# Iridium_9603N_Solar_Beacon.net
KiCad netlist of a schematic drawn in EAGLE
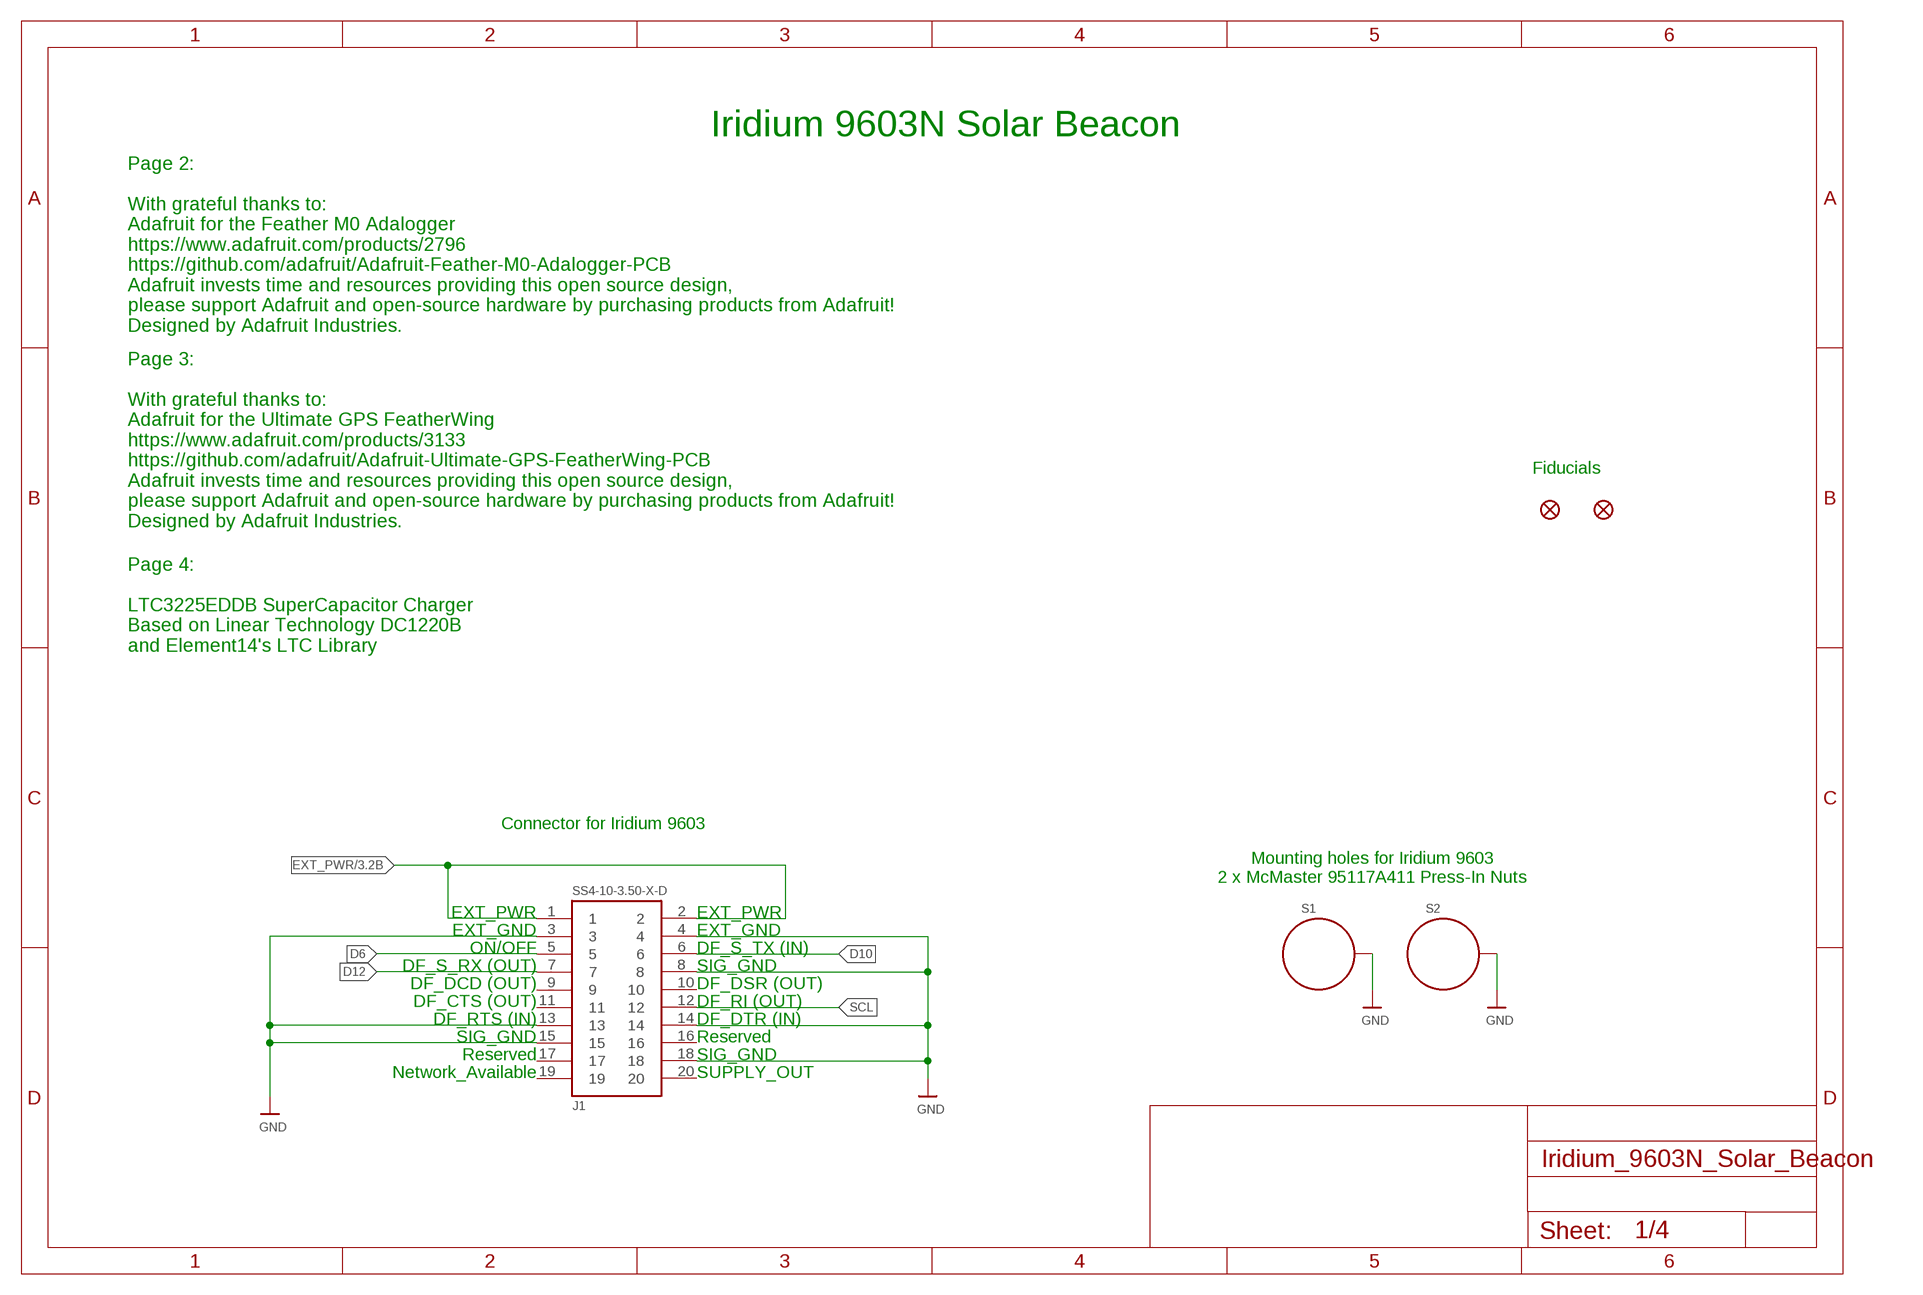
[diagram p0: schematic, sheet 1]
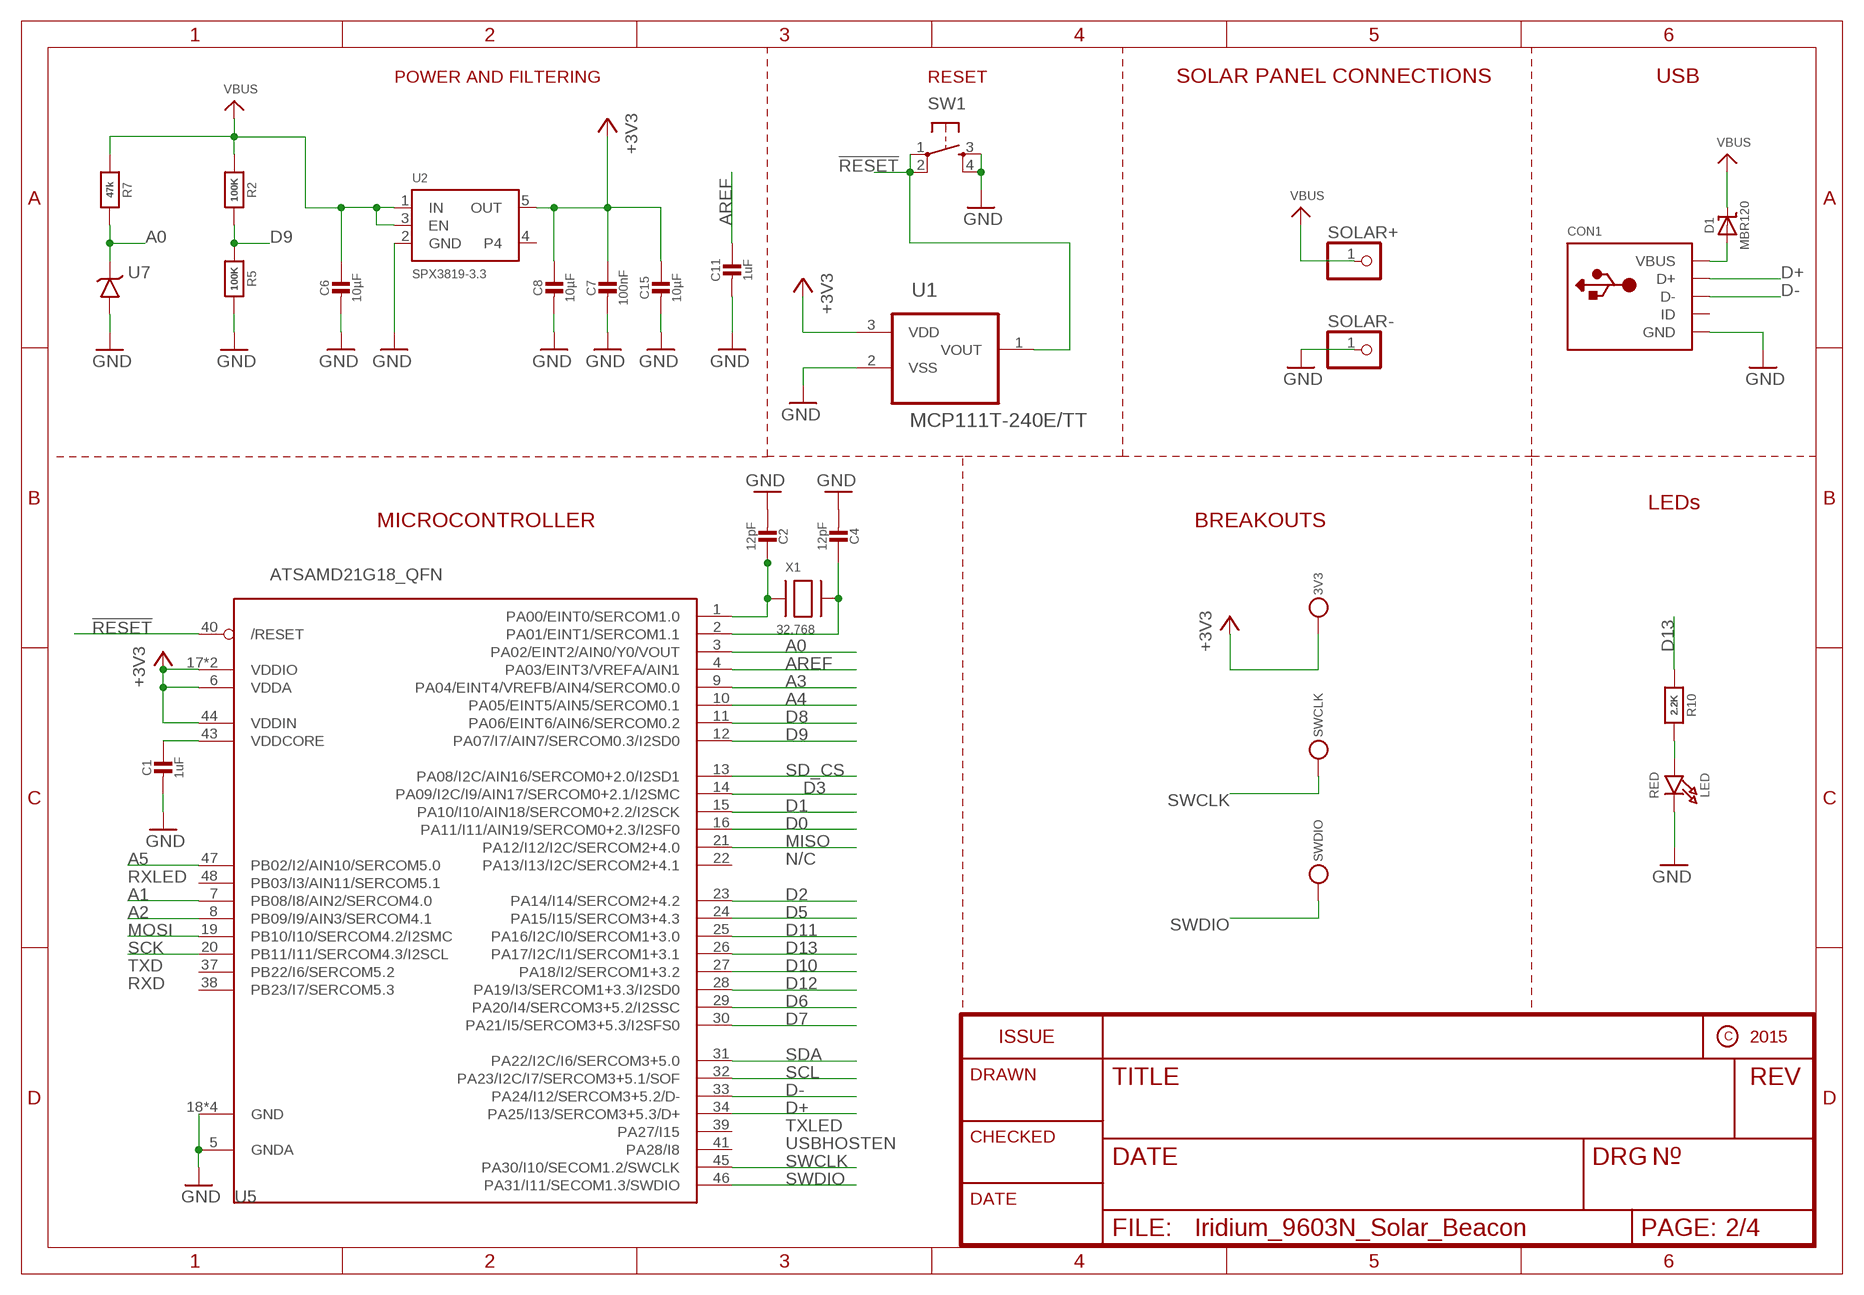
[diagram p1: schematic, sheet 2]
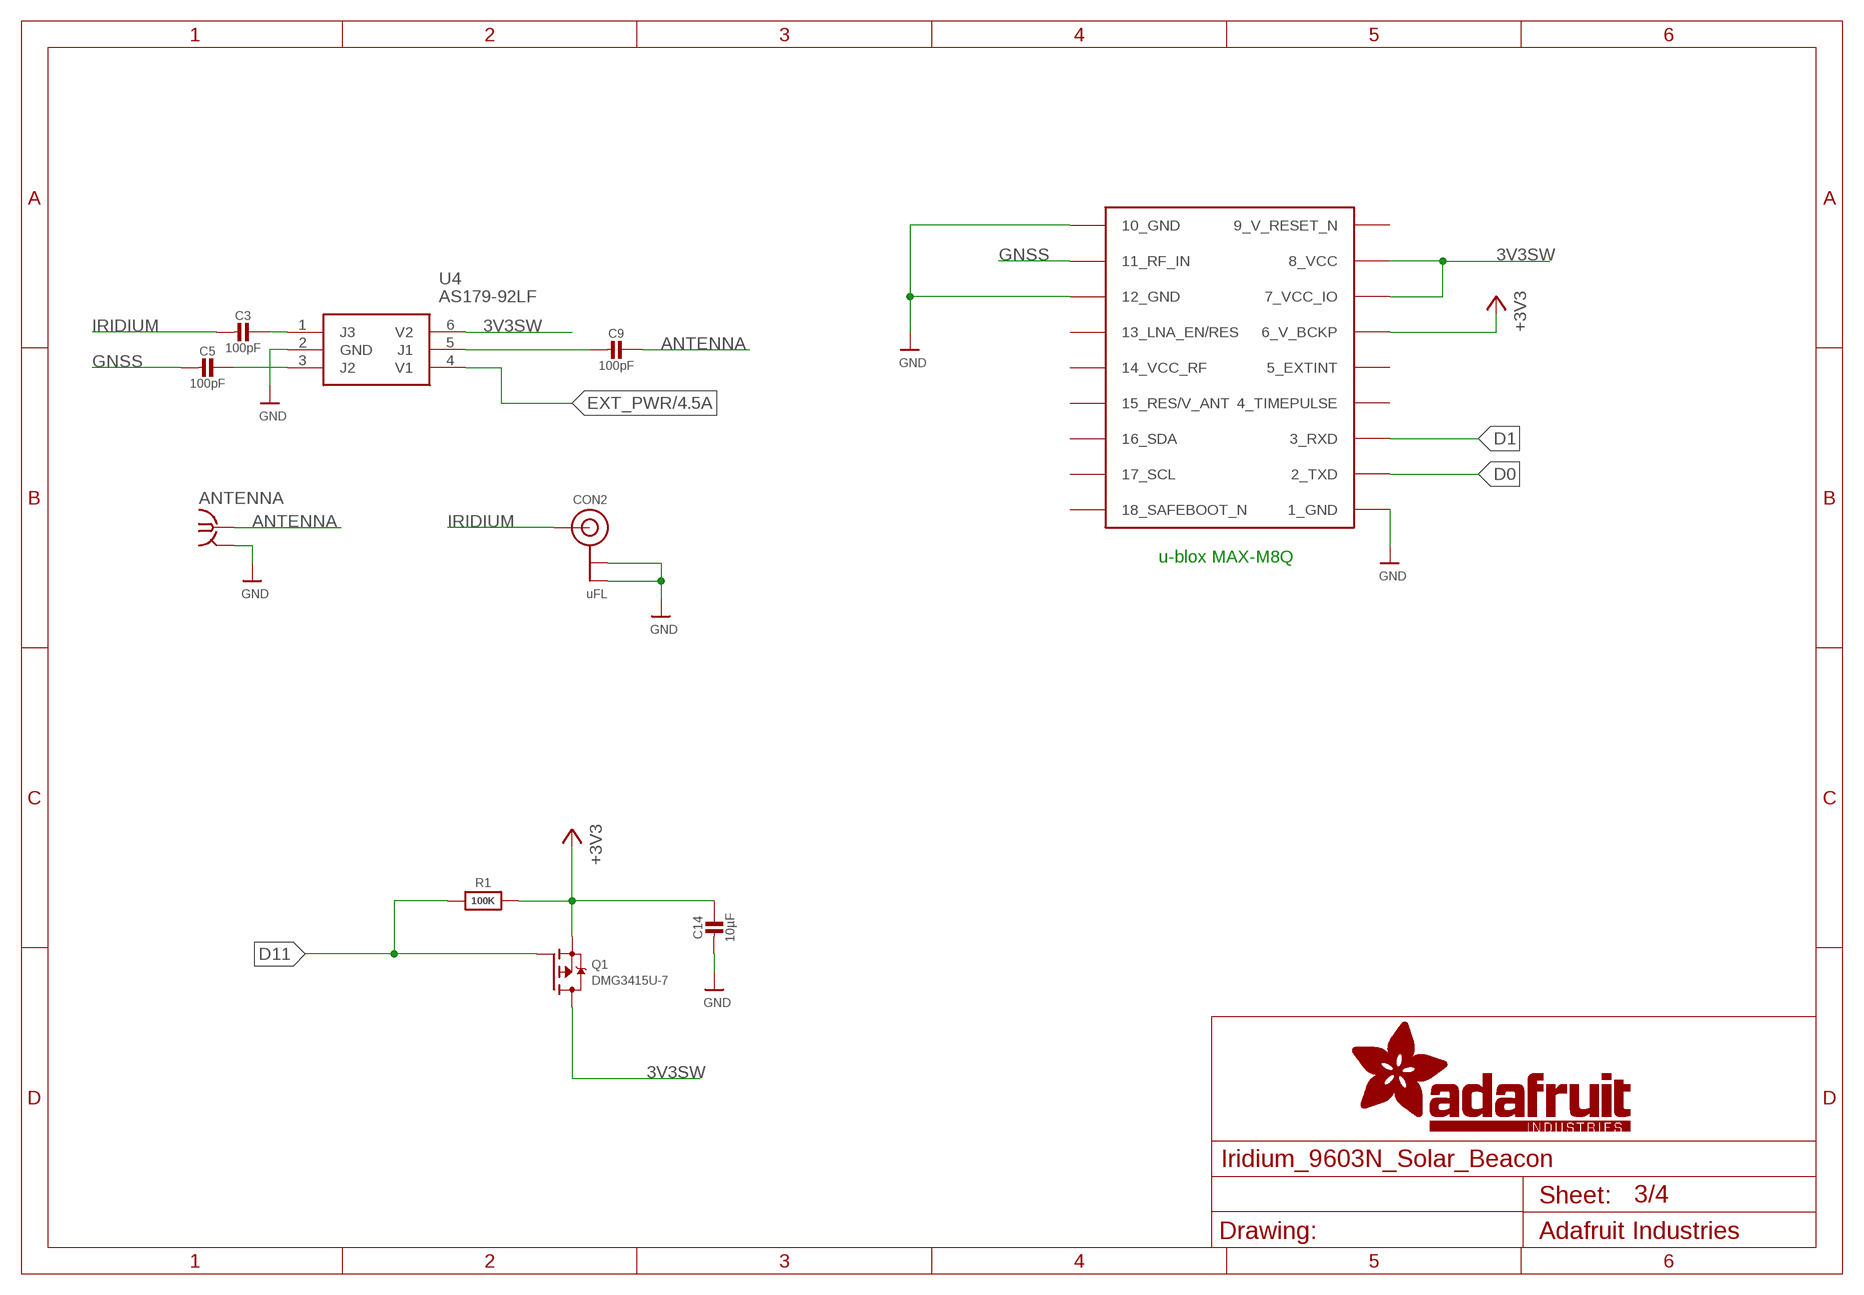
[diagram p2: schematic, sheet 3]
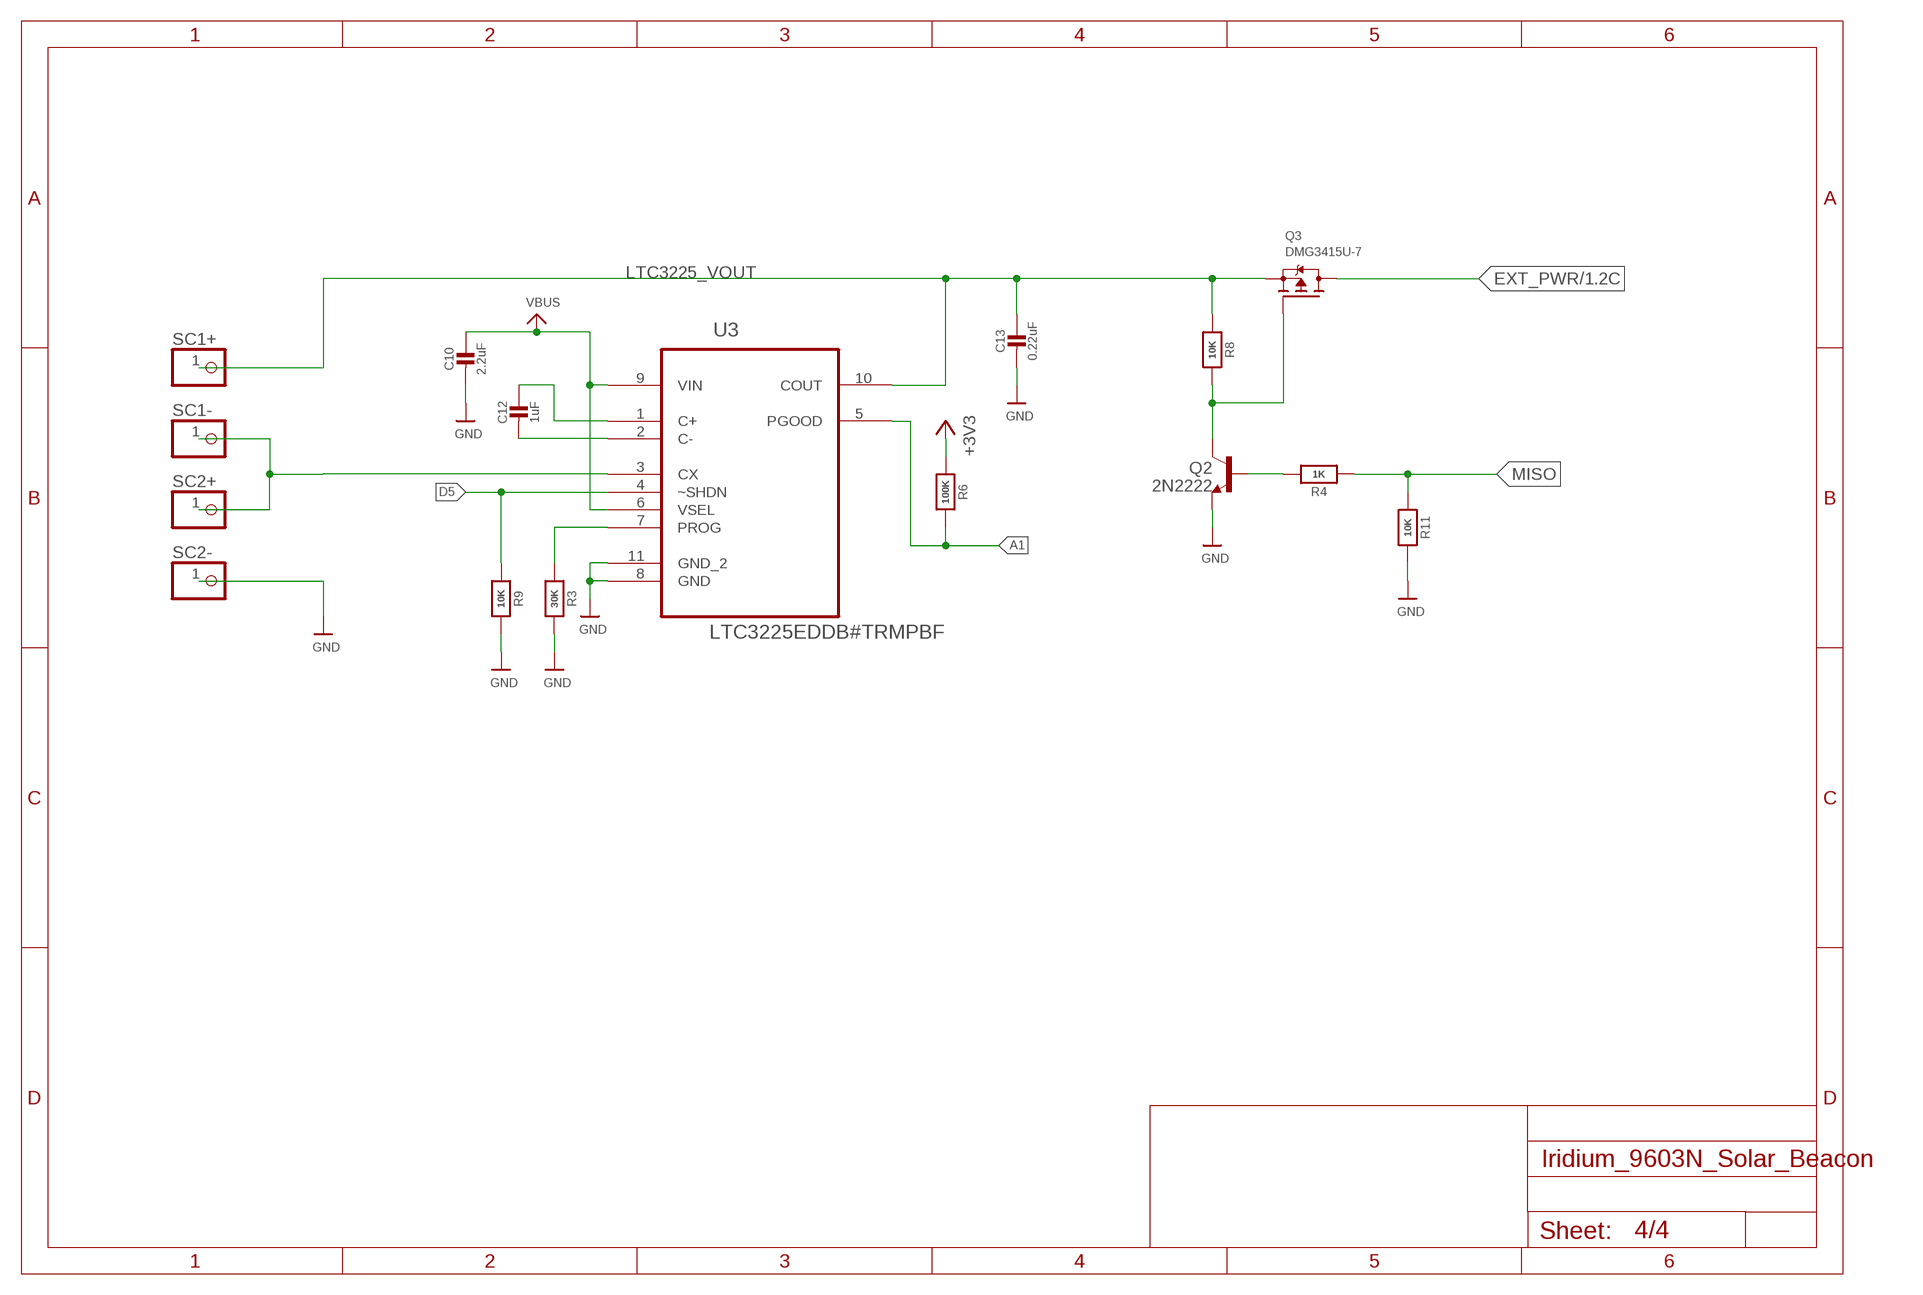
[diagram p3: schematic, sheet 4]

(export (version "E")
  (design (tool "Eeschema 10.0.6"))
  (components
    (comp (ref "FD1")
      (value "FIDUCIAL1X2")
      (footprint "eagle-import:FIDUCIAL-1X2")
      (libsource (lib "eagle-import") (part "FIDUCIAL1X2"))
    )
    (comp (ref "FD2")
      (value "FIDUCIAL1X2")
      (footprint "eagle-import:FIDUCIAL-1X2")
      (libsource (lib "eagle-import") (part "FIDUCIAL1X2"))
    )
    (comp (ref "J1")
      (value "SS4-10-3.50-X-D")
      (footprint "eagle-import:SS4-10-3.50-X-D")
      (libsource (lib "eagle-import") (part "SS4-10-3.50-X-D"))
    )
    (comp (ref "S1")
      (value "STANDOFF_ELECTRICALMCMASTER-95117A411")
      (footprint "eagle-import:STANDOFF-ELECTRICAL-MCMASTER-95117A411")
      (libsource (lib "eagle-import") (part "STANDOFF_ELECTRICALMCMASTER-95117A411"))
    )
    (comp (ref "S2")
      (value "STANDOFF_ELECTRICALMCMASTER-95117A411")
      (footprint "eagle-import:STANDOFF-ELECTRICAL-MCMASTER-95117A411")
      (libsource (lib "eagle-import") (part "STANDOFF_ELECTRICALMCMASTER-95117A411"))
    )
    (comp (ref "3V3")
      (value "TESTPOINTROUND1.5MM")
      (footprint "eagle-import:TESTPOINT_ROUND_1.5MM")
      (libsource (lib "eagle-import") (part "TESTPOINTROUND1.5MM"))
    )
    (comp (ref "C1")
      (value "1uF")
      (footprint "eagle-import:0603-NO")
      (libsource (lib "eagle-import") (part "CAP_CERAMIC0603_NO"))
    )
    (comp (ref "C2")
      (value "12pF")
      (footprint "eagle-import:0603-NO")
      (libsource (lib "eagle-import") (part "CAP_CERAMIC0603_NO"))
    )
    (comp (ref "C4")
      (value "12pF")
      (footprint "eagle-import:0603-NO")
      (libsource (lib "eagle-import") (part "CAP_CERAMIC0603_NO"))
    )
    (comp (ref "C6")
      (value "10µF")
      (footprint "eagle-import:0805-NO")
      (libsource (lib "eagle-import") (part "CAP_CERAMIC0805-NOOUTLINE"))
    )
    (comp (ref "C7")
      (value "100nF")
      (footprint "eagle-import:0603-NO")
      (libsource (lib "eagle-import") (part "CAP_CERAMIC0603_NO"))
    )
    (comp (ref "C8")
      (value "10µF")
      (footprint "eagle-import:0805-NO")
      (libsource (lib "eagle-import") (part "CAP_CERAMIC0805-NOOUTLINE"))
    )
    (comp (ref "C11")
      (value "1uF")
      (footprint "eagle-import:0603-NO")
      (libsource (lib "eagle-import") (part "CAP_CERAMIC0603_NO"))
    )
    (comp (ref "C15")
      (value "10µF")
      (footprint "eagle-import:0805-NO")
      (libsource (lib "eagle-import") (part "CAP_CERAMIC0805-NOOUTLINE"))
    )
    (comp (ref "CON1")
      (value "MICROBUILDER_USBFCI_10103594_CORRECTED")
      (footprint "eagle-import:MICROBUILDER_FCI_10103594_CORRECTED")
      (libsource (lib "eagle-import") (part "MICROBUILDER_USBFCI_10103594_CORRECTED"))
    )
    (comp (ref "D1")
      (value "MBR120")
      (footprint "eagle-import:SOD-123")
      (libsource (lib "eagle-import") (part "DIODE-SCHOTTKYSOD-123"))
    )
    (comp (ref "LED")
      (value "RED")
      (footprint "eagle-import:CHIPLED_0805_NOOUTLINE")
      (libsource (lib "eagle-import") (part "LED0805_NOOUTLINE"))
    )
    (comp (ref "R2")
      (value "100K")
      (footprint "eagle-import:0603-NO")
      (libsource (lib "eagle-import") (part "RESISTOR_0603_NOOUT"))
    )
    (comp (ref "R5")
      (value "100K")
      (footprint "eagle-import:0603-NO")
      (libsource (lib "eagle-import") (part "RESISTOR_0603_NOOUT"))
    )
    (comp (ref "R7")
      (value "47k")
      (footprint "eagle-import:0603-NO")
      (libsource (lib "eagle-import") (part "RESISTOR_0603_NOOUT"))
    )
    (comp (ref "R10")
      (value "2.2K")
      (footprint "eagle-import:0603-NO")
      (libsource (lib "eagle-import") (part "RESISTOR_0603_NOOUT"))
    )
    (comp (ref "SOLAR+")
      (value "PINHD-1X1")
      (footprint "eagle-import:1X01")
      (libsource (lib "eagle-import") (part "PINHD-1X1"))
    )
    (comp (ref "SOLAR-")
      (value "PINHD-1X1")
      (footprint "eagle-import:1X01")
      (libsource (lib "eagle-import") (part "PINHD-1X1"))
    )
    (comp (ref "SW1")
      (value "SWITCH_SPST_4_PINRECT")
      (footprint "eagle-import:TACTILE_SWITCH_SMD_4.6X2.8MM")
      (libsource (lib "eagle-import") (part "SWITCH_SPST_4_PINRECT"))
    )
    (comp (ref "SWCLK")
      (value "TESTPOINTROUND1.5MM")
      (footprint "eagle-import:TESTPOINT_ROUND_1.5MM")
      (libsource (lib "eagle-import") (part "TESTPOINTROUND1.5MM"))
    )
    (comp (ref "SWDIO")
      (value "TESTPOINTROUND1.5MM")
      (footprint "eagle-import:TESTPOINT_ROUND_1.5MM")
      (libsource (lib "eagle-import") (part "TESTPOINTROUND1.5MM"))
    )
    (comp (ref "U1")
      (value "MCP111T-240E/TT")
      (footprint "eagle-import:SOT95P237X112-3N")
      (fields (field (name "MPN") "MCP111T-270E/TT") (field (name "MPN_1") "MCP111T-240E/TT"))
      (libsource (lib "eagle-import") (part "MCP111T-270E/TT"))
    )
    (comp (ref "U2")
      (value "SPX3819-3.3")
      (footprint "eagle-import:SOT23-5")
      (libsource (lib "eagle-import") (part "VREG_SOT23-5"))
    )
    (comp (ref "U5")
      (value "ATSAMD21G18_QFN")
      (footprint "eagle-import:TQFN48_7MM")
      (libsource (lib "eagle-import") (part "ATSAMD21J_QFN"))
    )
    (comp (ref "U7")
      (value "LT1634-1,25BMCMS8")
      (footprint "eagle-import:MSOP8")
      (libsource (lib "eagle-import") (part "LT1634BMCMS8-1,25"))
    )
    (comp (ref "X1")
      (value "32.768")
      (footprint "eagle-import:XTAL3215")
      (libsource (lib "eagle-import") (part "XTAL-3.2X1.5"))
    )
    (comp (ref "ANTENNA")
      (value "SMA-142-0711-821/826")
      (footprint "eagle-import:J502-ND-142-0711-821_826")
      (fields (field (name "MF") "JOHNSON COMPONENTS") (field (name "MPN") "142-0711-821"))
      (libsource (lib "eagle-import") (part "SMA-142-0711-821/826"))
    )
    (comp (ref "C3")
      (value "100pF")
      (footprint "eagle-import:0603-NO")
      (libsource (lib "eagle-import") (part "CAP_CERAMIC0603_NO"))
    )
    (comp (ref "C5")
      (value "100pF")
      (footprint "eagle-import:0603-NO")
      (libsource (lib "eagle-import") (part "CAP_CERAMIC0603_NO"))
    )
    (comp (ref "C9")
      (value "100pF")
      (footprint "eagle-import:0603-NO")
      (libsource (lib "eagle-import") (part "CAP_CERAMIC0603_NO"))
    )
    (comp (ref "C14")
      (value "10µF")
      (footprint "eagle-import:0805-NO")
      (libsource (lib "eagle-import") (part "CAP_CERAMIC0805-NOOUTLINE"))
    )
    (comp (ref "CON2")
      (value "uFL")
      (footprint "eagle-import:U.FL")
      (libsource (lib "eagle-import") (part "ANTENNA_U.FL"))
    )
    (comp (ref "Q1")
      (value "DMG3415U-7")
      (footprint "eagle-import:SOT23-WIDE")
      (libsource (lib "eagle-import") (part "MOSFET-PWIDE"))
    )
    (comp (ref "R1")
      (value "100K")
      (footprint "eagle-import:0603-NO")
      (libsource (lib "eagle-import") (part "RESISTOR_0603_NOOUT"))
    )
    (comp (ref "U4")
      (value "AS179-92LF")
      (footprint "eagle-import:SOT65P220X100-6N")
      (libsource (lib "eagle-import") (part "AS179-92LF"))
    )
    (comp (ref "U6")
      (value "MAX-M8")
      (footprint "eagle-import:MAX-M8")
      (libsource (lib "eagle-import") (part "MAX-M8"))
    )
    (comp (ref "C10")
      (value "2.2uF")
      (footprint "eagle-import:0603-NO")
      (libsource (lib "eagle-import") (part "CAP_CERAMIC0603_NO"))
    )
    (comp (ref "C12")
      (value "1uF")
      (footprint "eagle-import:0603-NO")
      (libsource (lib "eagle-import") (part "CAP_CERAMIC0603_NO"))
    )
    (comp (ref "C13")
      (value "0.22uF")
      (footprint "eagle-import:0603-NO")
      (libsource (lib "eagle-import") (part "CAP_CERAMIC0603_NO"))
    )
    (comp (ref "Q2")
      (value "2N2222")
      (footprint "eagle-import:SOT23-BEC")
      (libsource (lib "eagle-import") (part "-NPN-SOT23-BECMMBT2222ALT1"))
    )
    (comp (ref "Q3")
      (value "DMG3415U-7")
      (footprint "eagle-import:SOT23-WIDE")
      (libsource (lib "eagle-import") (part "MOSFET-PWIDE"))
    )
    (comp (ref "R3")
      (value "30K")
      (footprint "eagle-import:0603-NO")
      (libsource (lib "eagle-import") (part "RESISTOR_0603_NOOUT"))
    )
    (comp (ref "R4")
      (value "1K")
      (footprint "eagle-import:0603-NO")
      (libsource (lib "eagle-import") (part "RESISTOR_0603_NOOUT"))
    )
    (comp (ref "R6")
      (value "100K")
      (footprint "eagle-import:0603-NO")
      (libsource (lib "eagle-import") (part "RESISTOR_0603_NOOUT"))
    )
    (comp (ref "R8")
      (value "10K")
      (footprint "eagle-import:0603-NO")
      (libsource (lib "eagle-import") (part "RESISTOR_0603_NOOUT"))
    )
    (comp (ref "R9")
      (value "10K")
      (footprint "eagle-import:0603-NO")
      (libsource (lib "eagle-import") (part "RESISTOR_0603_NOOUT"))
    )
    (comp (ref "R11")
      (value "10K")
      (footprint "eagle-import:0603-NO")
      (libsource (lib "eagle-import") (part "RESISTOR_0603_NOOUT"))
    )
    (comp (ref "SC1+")
      (value "PINHD-1X1")
      (footprint "eagle-import:1X01")
      (libsource (lib "eagle-import") (part "PINHD-1X1"))
    )
    (comp (ref "SC1-")
      (value "PINHD-1X1")
      (footprint "eagle-import:1X01")
      (libsource (lib "eagle-import") (part "PINHD-1X1"))
    )
    (comp (ref "SC2+")
      (value "PINHD-1X1")
      (footprint "eagle-import:1X01")
      (libsource (lib "eagle-import") (part "PINHD-1X1"))
    )
    (comp (ref "SC2-")
      (value "PINHD-1X1")
      (footprint "eagle-import:1X01")
      (libsource (lib "eagle-import") (part "PINHD-1X1"))
    )
    (comp (ref "U3")
      (value "LTC3225EDDB#TRMPBF")
      (footprint "eagle-import:DFN300X200-10L")
      (libsource (lib "eagle-import") (part "LTC3225EDDB-TRMPBFDFN300X200-10L"))
    )
  )
  (nets
    (net (code "1") (name "+3V3") (class "Default")
      (node (ref "3V3") (pin "P$1") (pinfunction "P$1_P$1") (pintype "bidirectional"))
      (node (ref "C14") (pin "1") (pinfunction "1_1") (pintype "passive"))
      (node (ref "C15") (pin "1") (pinfunction "1_1") (pintype "passive"))
      (node (ref "C7") (pin "1") (pinfunction "1_1") (pintype "passive"))
      (node (ref "C8") (pin "1") (pinfunction "1_1") (pintype "passive"))
      (node (ref "Q1") (pin "2") (pinfunction "S_2") (pintype "passive"))
      (node (ref "R1") (pin "2") (pinfunction "2_2") (pintype "passive"))
      (node (ref "R6") (pin "1") (pinfunction "1_1") (pintype "passive"))
      (node (ref "U1") (pin "3") (pinfunction "VDD_3") (pintype "power_in"))
      (node (ref "U2") (pin "5") (pinfunction "OUT_5") (pintype "power_in"))
      (node (ref "U5") (pin "17") (pinfunction "VDDIO_17") (pintype "power_in"))
      (node (ref "U5") (pin "36") (pinfunction "VDDIO_36") (pintype "power_in"))
      (node (ref "U5") (pin "44") (pinfunction "VDDIN_44") (pintype "power_in"))
      (node (ref "U5") (pin "6") (pinfunction "VDDA_6") (pintype "power_in"))
      (node (ref "U6") (pin "6_V_BCKP") (pinfunction "6_V_BCKP_6_V_BCKP") (pintype "bidirectional"))
    )
    (net (code "2") (name "3V3SW") (class "Default")
      (node (ref "Q1") (pin "3") (pinfunction "D_3") (pintype "passive"))
      (node (ref "U4") (pin "6") (pinfunction "V2_6") (pintype "bidirectional"))
      (node (ref "U6") (pin "7_VCC_IO") (pinfunction "7_VCC_IO_7_VCC_IO") (pintype "power_in"))
      (node (ref "U6") (pin "8_VCC") (pinfunction "8_VCC_8_VCC") (pintype "power_in"))
    )
    (net (code "3") (name "9_V_RESET_N") (class "Default")
      (node (ref "U6") (pin "9_RESET_N") (pinfunction "9_V_RESET_N_9_RESET_N") (pintype "power_in"))
    )
    (net (code "4") (name "A0") (class "Default")
      (node (ref "R7") (pin "2") (pinfunction "2_2") (pintype "passive"))
      (node (ref "U5") (pin "3") (pinfunction "PA02/EINT2/AIN0/Y0/VOUT_3") (pintype "bidirectional"))
      (node (ref "U7") (pin "6") (pinfunction "VOUT_6") (pintype "passive"))
    )
    (net (code "5") (name "A1") (class "Default")
      (node (ref "R6") (pin "2") (pinfunction "2_2") (pintype "passive"))
      (node (ref "U3") (pin "5") (pinfunction "PGOOD_5") (pintype "output"))
      (node (ref "U5") (pin "7") (pinfunction "PB08/I8/AIN2/SERCOM4.0_7") (pintype "bidirectional"))
    )
    (net (code "6") (name "A2") (class "Default")
      (node (ref "U5") (pin "8") (pinfunction "PB09/I9/AIN3/SERCOM4.1_8") (pintype "bidirectional"))
    )
    (net (code "7") (name "A3") (class "Default")
      (node (ref "U5") (pin "9") (pinfunction "PA04/EINT4/VREFB/AIN4/SERCOM0.0_9") (pintype "bidirectional"))
    )
    (net (code "8") (name "A4") (class "Default")
      (node (ref "U5") (pin "10") (pinfunction "PA05/EINT5/AIN5/SERCOM0.1_10") (pintype "bidirectional"))
    )
    (net (code "9") (name "A5") (class "Default")
      (node (ref "U5") (pin "47") (pinfunction "PB02/I2/AIN10/SERCOM5.0_47") (pintype "bidirectional"))
    )
    (net (code "10") (name "ANTENNA") (class "Default")
      (node (ref "ANTENNA") (pin "1") (pinfunction "1_1") (pintype "passive"))
      (node (ref "C9") (pin "1") (pinfunction "1_1") (pintype "passive"))
    )
    (net (code "11") (name "AREF") (class "Default")
      (node (ref "C11") (pin "1") (pinfunction "1_1") (pintype "passive"))
      (node (ref "U5") (pin "4") (pinfunction "PA03/EINT3/VREFA/AIN1_4") (pintype "bidirectional"))
    )
    (net (code "12") (name "D+") (class "Default")
      (node (ref "CON1") (pin "D+") (pinfunction "D+_D+") (pintype "bidirectional"))
      (node (ref "U5") (pin "34") (pinfunction "PA25/I13/SERCOM3+5.3/D+_34") (pintype "bidirectional"))
    )
    (net (code "13") (name "D-") (class "Default")
      (node (ref "CON1") (pin "D-") (pinfunction "D-_D-") (pintype "bidirectional"))
      (node (ref "U5") (pin "33") (pinfunction "PA24/I12/SERCOM3+5.2/D-_33") (pintype "bidirectional"))
    )
    (net (code "14") (name "D0") (class "Default")
      (node (ref "U5") (pin "16") (pinfunction "PA11/I11/AIN19/SERCOM0+2.3/I2SF0_16") (pintype "bidirectional"))
      (node (ref "U6") (pin "2_TXD") (pinfunction "2_TXD_2_TXD") (pintype "bidirectional"))
    )
    (net (code "15") (name "D1") (class "Default")
      (node (ref "U5") (pin "15") (pinfunction "PA10/I10/AIN18/SERCOM0+2.2/I2SCK_15") (pintype "bidirectional"))
      (node (ref "U6") (pin "3_RXD") (pinfunction "3_RXD_3_RXD") (pintype "bidirectional"))
    )
    (net (code "16") (name "D2") (class "Default")
      (node (ref "U5") (pin "23") (pinfunction "PA14/I14/SERCOM2+4.2_23") (pintype "bidirectional"))
    )
    (net (code "17") (name "D3") (class "Default")
      (node (ref "U5") (pin "14") (pinfunction "PA09/I2C/I9/AIN17/SERCOM0+2.1/I2SMC_14") (pintype "bidirectional"))
    )
    (net (code "18") (name "D5") (class "Default")
      (node (ref "R9") (pin "1") (pinfunction "1_1") (pintype "passive"))
      (node (ref "U3") (pin "4") (pinfunction "~{SHDN}_4") (pintype "input"))
      (node (ref "U5") (pin "24") (pinfunction "PA15/I15/SERCOM3+4.3_24") (pintype "bidirectional"))
    )
    (net (code "19") (name "D6") (class "Default")
      (node (ref "J1") (pin "5") (pinfunction "5_5") (pintype "bidirectional"))
      (node (ref "U5") (pin "29") (pinfunction "PA20/I4/SERCOM3+5.2/I2SSC_29") (pintype "bidirectional"))
    )
    (net (code "20") (name "D7") (class "Default")
      (node (ref "U5") (pin "30") (pinfunction "PA21/I5/SERCOM3+5.3/I2SFS0_30") (pintype "bidirectional"))
    )
    (net (code "21") (name "D8") (class "Default")
      (node (ref "U5") (pin "11") (pinfunction "PA06/EINT6/AIN6/SERCOM0.2_11") (pintype "bidirectional"))
    )
    (net (code "22") (name "D9") (class "Default")
      (node (ref "R2") (pin "2") (pinfunction "2_2") (pintype "passive"))
      (node (ref "R5") (pin "1") (pinfunction "1_1") (pintype "passive"))
      (node (ref "U5") (pin "12") (pinfunction "PA07/I7/AIN7/SERCOM0.3/I2SD0_12") (pintype "bidirectional"))
    )
    (net (code "23") (name "D10") (class "Default")
      (node (ref "J1") (pin "6") (pinfunction "6_6") (pintype "bidirectional"))
      (node (ref "U5") (pin "27") (pinfunction "PA18/I2/SERCOM1+3.2_27") (pintype "bidirectional"))
    )
    (net (code "24") (name "D11") (class "Default")
      (node (ref "Q1") (pin "1") (pinfunction "G_1") (pintype "passive"))
      (node (ref "R1") (pin "1") (pinfunction "1_1") (pintype "passive"))
      (node (ref "U5") (pin "25") (pinfunction "PA16/I2C/I0/SERCOM1+3.0_25") (pintype "bidirectional"))
    )
    (net (code "25") (name "D12") (class "Default")
      (node (ref "J1") (pin "7") (pinfunction "7_7") (pintype "bidirectional"))
      (node (ref "U5") (pin "28") (pinfunction "PA19/I3/SERCOM1+3.3/I2SD0_28") (pintype "bidirectional"))
    )
    (net (code "26") (name "D13") (class "Default")
      (node (ref "R10") (pin "1") (pinfunction "1_1") (pintype "passive"))
      (node (ref "U5") (pin "26") (pinfunction "PA17/I2C/I1/SERCOM1+3.1_26") (pintype "bidirectional"))
    )
    (net (code "27") (name "EXT_PWR") (class "Default")
      (node (ref "J1") (pin "1") (pinfunction "1_1") (pintype "bidirectional"))
      (node (ref "J1") (pin "2") (pinfunction "2_2") (pintype "bidirectional"))
      (node (ref "Q3") (pin "3") (pinfunction "D_3") (pintype "passive"))
      (node (ref "U4") (pin "4") (pinfunction "V1_4") (pintype "bidirectional"))
    )
    (net (code "28") (name "GND") (class "Default")
      (node (ref "ANTENNA") (pin "G@1") (pinfunction "2_G@1") (pintype "passive"))
      (node (ref "ANTENNA") (pin "G@2") (pinfunction "2_G@2") (pintype "passive"))
      (node (ref "ANTENNA") (pin "G@3") (pinfunction "2_G@3") (pintype "passive"))
      (node (ref "ANTENNA") (pin "G@4") (pinfunction "2_G@4") (pintype "passive"))
      (node (ref "C1") (pin "2") (pinfunction "2_2") (pintype "passive"))
      (node (ref "C10") (pin "2") (pinfunction "2_2") (pintype "passive"))
      (node (ref "C11") (pin "2") (pinfunction "2_2") (pintype "passive"))
      (node (ref "C13") (pin "2") (pinfunction "2_2") (pintype "passive"))
      (node (ref "C14") (pin "2") (pinfunction "2_2") (pintype "passive"))
      (node (ref "C15") (pin "2") (pinfunction "2_2") (pintype "passive"))
      (node (ref "C2") (pin "2") (pinfunction "2_2") (pintype "passive"))
      (node (ref "C4") (pin "2") (pinfunction "2_2") (pintype "passive"))
      (node (ref "C6") (pin "2") (pinfunction "2_2") (pintype "passive"))
      (node (ref "C7") (pin "2") (pinfunction "2_2") (pintype "passive"))
      (node (ref "C8") (pin "2") (pinfunction "2_2") (pintype "passive"))
      (node (ref "CON1") (pin "BASE@1") (pinfunction "GND_BASE@1") (pintype "power_in"))
      (node (ref "CON1") (pin "BASE@2") (pinfunction "GND_BASE@2") (pintype "power_in"))
      (node (ref "CON1") (pin "GND") (pinfunction "GND_GND") (pintype "power_in"))
      (node (ref "CON1") (pin "SPRT@1") (pinfunction "GND_SPRT@1") (pintype "power_in"))
      (node (ref "CON1") (pin "SPRT@2") (pinfunction "GND_SPRT@2") (pintype "power_in"))
      (node (ref "CON1") (pin "SPRT@3") (pinfunction "GND_SPRT@3") (pintype "power_in"))
      (node (ref "CON1") (pin "SPRT@4") (pinfunction "GND_SPRT@4") (pintype "power_in"))
      (node (ref "CON2") (pin "1") (pinfunction "GND_1") (pintype "passive"))
      (node (ref "CON2") (pin "2") (pinfunction "GND_2") (pintype "passive"))
      (node (ref "J1") (pin "13") (pinfunction "13_13") (pintype "bidirectional"))
      (node (ref "J1") (pin "14") (pinfunction "14_14") (pintype "bidirectional"))
      (node (ref "J1") (pin "15") (pinfunction "15_15") (pintype "bidirectional"))
      (node (ref "J1") (pin "18") (pinfunction "18_18") (pintype "bidirectional"))
      (node (ref "J1") (pin "3") (pinfunction "3_3") (pintype "bidirectional"))
      (node (ref "J1") (pin "4") (pinfunction "4_4") (pintype "bidirectional"))
      (node (ref "J1") (pin "8") (pinfunction "8_8") (pintype "bidirectional"))
      (node (ref "LED") (pin "C") (pinfunction "C_C") (pintype "passive"))
      (node (ref "Q2") (pin "E") (pinfunction "E_E") (pintype "passive"))
      (node (ref "R11") (pin "2") (pinfunction "2_2") (pintype "passive"))
      (node (ref "R3") (pin "2") (pinfunction "2_2") (pintype "passive"))
      (node (ref "R5") (pin "2") (pinfunction "2_2") (pintype "passive"))
      (node (ref "R9") (pin "2") (pinfunction "2_2") (pintype "passive"))
      (node (ref "S1") (pin "P1") (pinfunction "P$1_P1") (pintype "bidirectional"))
      (node (ref "S2") (pin "P1") (pinfunction "P$1_P1") (pintype "bidirectional"))
      (node (ref "SC2-") (pin "1") (pinfunction "1_1") (pintype "passive"))
      (node (ref "SOLAR-") (pin "1") (pinfunction "1_1") (pintype "passive"))
      (node (ref "SW1") (pin "3") (pinfunction "3_3") (pintype "passive"))
      (node (ref "SW1") (pin "4") (pinfunction "4_4") (pintype "passive"))
      (node (ref "U1") (pin "2") (pinfunction "VSS_2") (pintype "power_in"))
      (node (ref "U2") (pin "2") (pinfunction "GND_2") (pintype "power_in"))
      (node (ref "U3") (pin "11") (pinfunction "GND_2_11") (pintype "passive"))
      (node (ref "U3") (pin "8") (pinfunction "GND_8") (pintype "passive"))
      (node (ref "U4") (pin "2") (pinfunction "GND_2") (pintype "bidirectional"))
      (node (ref "U5") (pin "18") (pinfunction "GND_18") (pintype "power_in"))
      (node (ref "U5") (pin "35") (pinfunction "GND_35") (pintype "power_in"))
      (node (ref "U5") (pin "42") (pinfunction "GND_42") (pintype "power_in"))
      (node (ref "U5") (pin "5") (pinfunction "GNDA_5") (pintype "power_in"))
      (node (ref "U5") (pin "THERMAL") (pinfunction "GND_THERMAL") (pintype "power_in"))
      (node (ref "U6") (pin "10_GND") (pinfunction "10_GND_10_GND") (pintype "power_in"))
      (node (ref "U6") (pin "12_GND") (pinfunction "12_GND_12_GND") (pintype "power_in"))
      (node (ref "U6") (pin "1_GND") (pinfunction "1_GND_1_GND") (pintype "power_in"))
      (node (ref "U7") (pin "4") (pinfunction "GND_4") (pintype "passive"))
    )
    (net (code "29") (name "GNSS") (class "Default")
      (node (ref "C5") (pin "2") (pinfunction "2_2") (pintype "passive"))
      (node (ref "U6") (pin "11_RF_IN") (pinfunction "11_RF_IN_11_RF_IN") (pintype "bidirectional"))
    )
    (net (code "30") (name "IRIDIUM") (class "Default")
      (node (ref "C3") (pin "2") (pinfunction "2_2") (pintype "passive"))
      (node (ref "CON2") (pin "3") (pinfunction "SIGNAL_3") (pintype "passive"))
    )
    (net (code "31") (name "LTC3225_VOUT") (class "Default")
      (node (ref "C13") (pin "1") (pinfunction "1_1") (pintype "passive"))
      (node (ref "Q3") (pin "2") (pinfunction "S_2") (pintype "passive"))
      (node (ref "R8") (pin "1") (pinfunction "1_1") (pintype "passive"))
      (node (ref "SC1+") (pin "1") (pinfunction "1_1") (pintype "passive"))
      (node (ref "U3") (pin "10") (pinfunction "COUT_10") (pintype "output"))
    )
    (net (code "32") (name "MISO") (class "Default")
      (node (ref "R11") (pin "1") (pinfunction "1_1") (pintype "passive"))
      (node (ref "R4") (pin "1") (pinfunction "1_1") (pintype "passive"))
      (node (ref "U5") (pin "21") (pinfunction "PA12/I12/I2C/SERCOM2+4.0_21") (pintype "bidirectional"))
    )
    (net (code "33") (name "MOSI") (class "Default")
      (node (ref "U5") (pin "19") (pinfunction "PB10/I10/SERCOM4.2/I2SMC_19") (pintype "bidirectional"))
    )
    (net (code "34") (name "Net-(CON1-PadVBUS)") (class "Default")
      (node (ref "CON1") (pin "VBUS") (pinfunction "VBUS_VBUS") (pintype "power_in"))
      (node (ref "D1") (pin "A") (pinfunction "A_A") (pintype "passive"))
    )
    (net (code "35") (name "Net-(LED-PadA)") (class "Default")
      (node (ref "LED") (pin "A") (pinfunction "A_A") (pintype "passive"))
      (node (ref "R10") (pin "2") (pinfunction "2_2") (pintype "passive"))
    )
    (net (code "36") (name "Net-(Q2-PadB)") (class "Default")
      (node (ref "Q2") (pin "B") (pinfunction "B_B") (pintype "passive"))
      (node (ref "R4") (pin "2") (pinfunction "2_2") (pintype "passive"))
    )
    (net (code "37") (name "Net-(Q3-G)") (class "Default")
      (node (ref "Q2") (pin "C") (pinfunction "C_C") (pintype "passive"))
      (node (ref "Q3") (pin "1") (pinfunction "G_1") (pintype "passive"))
      (node (ref "R8") (pin "2") (pinfunction "2_2") (pintype "passive"))
    )
    (net (code "38") (name "Net-(U3-C+)") (class "Default")
      (node (ref "C12") (pin "1") (pinfunction "1_1") (pintype "passive"))
      (node (ref "U3") (pin "1") (pinfunction "C+_1") (pintype "passive"))
    )
    (net (code "39") (name "Net-(U3-C-)") (class "Default")
      (node (ref "C12") (pin "2") (pinfunction "2_2") (pintype "passive"))
      (node (ref "U3") (pin "2") (pinfunction "C-_2") (pintype "passive"))
    )
    (net (code "40") (name "Net-(U3-CX)") (class "Default")
      (node (ref "SC1-") (pin "1") (pinfunction "1_1") (pintype "passive"))
      (node (ref "SC2+") (pin "1") (pinfunction "1_1") (pintype "passive"))
      (node (ref "U3") (pin "3") (pinfunction "CX_3") (pintype "passive"))
    )
    (net (code "41") (name "Net-(U3-PROG)") (class "Default")
      (node (ref "R3") (pin "1") (pinfunction "1_1") (pintype "passive"))
      (node (ref "U3") (pin "7") (pinfunction "PROG_7") (pintype "input"))
    )
    (net (code "42") (name "Net-(U4-J1)") (class "Default")
      (node (ref "C9") (pin "2") (pinfunction "2_2") (pintype "passive"))
      (node (ref "U4") (pin "5") (pinfunction "J1_5") (pintype "bidirectional"))
    )
    (net (code "43") (name "Net-(U4-J2)") (class "Default")
      (node (ref "C5") (pin "1") (pinfunction "1_1") (pintype "passive"))
      (node (ref "U4") (pin "3") (pinfunction "J2_3") (pintype "bidirectional"))
    )
    (net (code "44") (name "Net-(U4-J3)") (class "Default")
      (node (ref "C3") (pin "1") (pinfunction "1_1") (pintype "passive"))
      (node (ref "U4") (pin "1") (pinfunction "J3_1") (pintype "bidirectional"))
    )
    (net (code "45") (name "Net-(U5-PA00{slash}EINT0{slash}SERCOM1.0)") (class "Default")
      (node (ref "C2") (pin "1") (pinfunction "1_1") (pintype "passive"))
      (node (ref "U5") (pin "1") (pinfunction "PA00/EINT0/SERCOM1.0_1") (pintype "bidirectional"))
      (node (ref "X1") (pin "P$1") (pinfunction "P$1_P$1") (pintype "bidirectional"))
    )
    (net (code "46") (name "Net-(U5-PA01{slash}EINT1{slash}SERCOM1.1)") (class "Default")
      (node (ref "C4") (pin "1") (pinfunction "1_1") (pintype "passive"))
      (node (ref "U5") (pin "2") (pinfunction "PA01/EINT1/SERCOM1.1_2") (pintype "bidirectional"))
      (node (ref "X1") (pin "P$2") (pinfunction "P$2_P$2") (pintype "bidirectional"))
    )
    (net (code "47") (name "Net-(U5-VDDCORE)") (class "Default")
      (node (ref "C1") (pin "1") (pinfunction "1_1") (pintype "passive"))
      (node (ref "U5") (pin "43") (pinfunction "VDDCORE_43") (pintype "power_in"))
    )
    (net (code "48") (name "SCK") (class "Default")
      (node (ref "U5") (pin "20") (pinfunction "PB11/I11/SERCOM4.3/I2SCL_20") (pintype "bidirectional"))
    )
    (net (code "49") (name "SCL") (class "Default")
      (node (ref "J1") (pin "12") (pinfunction "12_12") (pintype "bidirectional"))
      (node (ref "U5") (pin "32") (pinfunction "PA23/I2C/I7/SERCOM3+5.1/SOF_32") (pintype "bidirectional"))
    )
    (net (code "50") (name "SDA") (class "Default")
      (node (ref "U5") (pin "31") (pinfunction "PA22/I2C/I6/SERCOM3+5.0_31") (pintype "bidirectional"))
    )
    (net (code "51") (name "SD_CS") (class "Default")
      (node (ref "U5") (pin "13") (pinfunction "PA08/I2C/AIN16/SERCOM0+2.0/I2SD1_13") (pintype "bidirectional"))
    )
    (net (code "52") (name "SWCLK") (class "Default")
      (node (ref "SWCLK") (pin "P$1") (pinfunction "P$1_P$1") (pintype "bidirectional"))
      (node (ref "U5") (pin "45") (pinfunction "PA30/I10/SECOM1.2/SWCLK_45") (pintype "bidirectional"))
    )
    (net (code "53") (name "SWDIO") (class "Default")
      (node (ref "SWDIO") (pin "P$1") (pinfunction "P$1_P$1") (pintype "bidirectional"))
      (node (ref "U5") (pin "46") (pinfunction "PA31/I11/SECOM1.3/SWDIO_46") (pintype "bidirectional"))
    )
    (net (code "54") (name "VBUS") (class "Default")
      (node (ref "C10") (pin "1") (pinfunction "1_1") (pintype "passive"))
      (node (ref "C6") (pin "1") (pinfunction "1_1") (pintype "passive"))
      (node (ref "D1") (pin "C") (pinfunction "C_C") (pintype "passive"))
      (node (ref "R2") (pin "1") (pinfunction "1_1") (pintype "passive"))
      (node (ref "R7") (pin "1") (pinfunction "1_1") (pintype "passive"))
      (node (ref "SOLAR+") (pin "1") (pinfunction "1_1") (pintype "passive"))
      (node (ref "U2") (pin "1") (pinfunction "IN_1") (pintype "power_in"))
      (node (ref "U2") (pin "3") (pinfunction "EN_3") (pintype "input"))
      (node (ref "U3") (pin "6") (pinfunction "VSEL_6") (pintype "input"))
      (node (ref "U3") (pin "9") (pinfunction "VIN_9") (pintype "power_in"))
    )
    (net (code "55") (name "unconnected-(CON1-PadID)") (class "Default")
      (node (ref "CON1") (pin "ID") (pinfunction "ID_ID") (pintype "bidirectional"))
    )
    (net (code "56") (name "unconnected-(J1-Pad9)") (class "Default")
      (node (ref "J1") (pin "9") (pinfunction "9_9") (pintype "bidirectional"))
    )
    (net (code "57") (name "unconnected-(J1-Pad10)") (class "Default")
      (node (ref "J1") (pin "10") (pinfunction "10_10") (pintype "bidirectional"))
    )
    (net (code "58") (name "unconnected-(J1-Pad11)") (class "Default")
      (node (ref "J1") (pin "11") (pinfunction "11_11") (pintype "bidirectional"))
    )
    (net (code "59") (name "unconnected-(J1-Pad16)") (class "Default")
      (node (ref "J1") (pin "16") (pinfunction "16_16") (pintype "bidirectional"))
    )
    (net (code "60") (name "unconnected-(J1-Pad17)") (class "Default")
      (node (ref "J1") (pin "17") (pinfunction "17_17") (pintype "bidirectional"))
    )
    (net (code "61") (name "unconnected-(J1-Pad19)") (class "Default")
      (node (ref "J1") (pin "19") (pinfunction "19_19") (pintype "bidirectional"))
    )
    (net (code "62") (name "unconnected-(J1-Pad20)") (class "Default")
      (node (ref "J1") (pin "20") (pinfunction "20_20") (pintype "bidirectional"))
    )
    (net (code "63") (name "unconnected-(U2-P4-Pad4)") (class "Default")
      (node (ref "U2") (pin "4") (pinfunction "P4_4") (pintype "bidirectional"))
    )
    (net (code "64") (name "unconnected-(U5-PA13{slash}I13{slash}I2C{slash}SERCOM2+4.1-Pad22)") (class "Default")
      (node (ref "U5") (pin "22") (pinfunction "PA13/I13/I2C/SERCOM2+4.1_22") (pintype "bidirectional"))
    )
    (net (code "65") (name "unconnected-(U5-PA27{slash}I15-Pad39)") (class "Default")
      (node (ref "U5") (pin "39") (pinfunction "PA27/I15_39") (pintype "bidirectional"))
    )
    (net (code "66") (name "unconnected-(U5-PA28{slash}I8-Pad41)") (class "Default")
      (node (ref "U5") (pin "41") (pinfunction "PA28/I8_41") (pintype "bidirectional"))
    )
    (net (code "67") (name "unconnected-(U5-PB03{slash}I3{slash}AIN11{slash}SERCOM5.1-Pad48)") (class "Default")
      (node (ref "U5") (pin "48") (pinfunction "PB03/I3/AIN11/SERCOM5.1_48") (pintype "bidirectional"))
    )
    (net (code "68") (name "unconnected-(U5-PB22{slash}I6{slash}SERCOM5.2-Pad37)") (class "Default")
      (node (ref "U5") (pin "37") (pinfunction "PB22/I6/SERCOM5.2_37") (pintype "bidirectional"))
    )
    (net (code "69") (name "unconnected-(U5-PB23{slash}I7{slash}SERCOM5.3-Pad38)") (class "Default")
      (node (ref "U5") (pin "38") (pinfunction "PB23/I7/SERCOM5.3_38") (pintype "bidirectional"))
    )
    (net (code "70") (name "unconnected-(U6-13_LNA_EN{slash}RES-Pad13_LNA_EN)") (class "Default")
      (node (ref "U6") (pin "13_LNA_EN") (pinfunction "13_LNA_EN/RES_13_LNA_EN") (pintype "bidirectional"))
    )
    (net (code "71") (name "unconnected-(U6-15_RES{slash}V_ANT-Pad15_V_ANT{slash}RESERVED)") (class "Default")
      (node (ref "U6") (pin "15_V_ANT/RESERVED") (pinfunction "15_RES/V_ANT_15_V_ANT/RESERVED") (pintype "bidirectional"))
    )
    (net (code "72") (name "unconnected-(U6-Pad4_TIMEPULSE)") (class "Default")
      (node (ref "U6") (pin "4_TIMEPULSE") (pinfunction "4_TIMEPULSE_4_TIMEPULSE") (pintype "bidirectional"))
    )
    (net (code "73") (name "unconnected-(U6-Pad5_EXTINT)") (class "Default")
      (node (ref "U6") (pin "5_EXTINT") (pinfunction "5_EXTINT_5_EXTINT") (pintype "bidirectional"))
    )
    (net (code "74") (name "unconnected-(U6-Pad14_VCC_RF)") (class "Default")
      (node (ref "U6") (pin "14_VCC_RF") (pinfunction "14_VCC_RF_14_VCC_RF") (pintype "bidirectional"))
    )
    (net (code "75") (name "unconnected-(U6-Pad16_SDA)") (class "Default")
      (node (ref "U6") (pin "16_SDA") (pinfunction "16_SDA_16_SDA") (pintype "bidirectional"))
    )
    (net (code "76") (name "unconnected-(U6-Pad17_SCL)") (class "Default")
      (node (ref "U6") (pin "17_SCL") (pinfunction "17_SCL_17_SCL") (pintype "bidirectional"))
    )
    (net (code "77") (name "unconnected-(U6-Pad18_SAFEBOOT_N)") (class "Default")
      (node (ref "U6") (pin "18_SAFEBOOT_N") (pinfunction "18_SAFEBOOT_N_18_SAFEBOOT_N") (pintype "bidirectional"))
    )
    (net (code "78") (name "~{RESET}") (class "Default")
      (node (ref "SW1") (pin "1") (pinfunction "1_1") (pintype "passive"))
      (node (ref "SW1") (pin "2") (pinfunction "2_2") (pintype "passive"))
      (node (ref "U1") (pin "1") (pinfunction "VOUT_1") (pintype "output"))
      (node (ref "U5") (pin "40") (pinfunction "/RESET_40") (pintype "bidirectional"))
    )
  )
)
